# I2c.net
KiCad netlist of a schematic drawn in Altium Designer
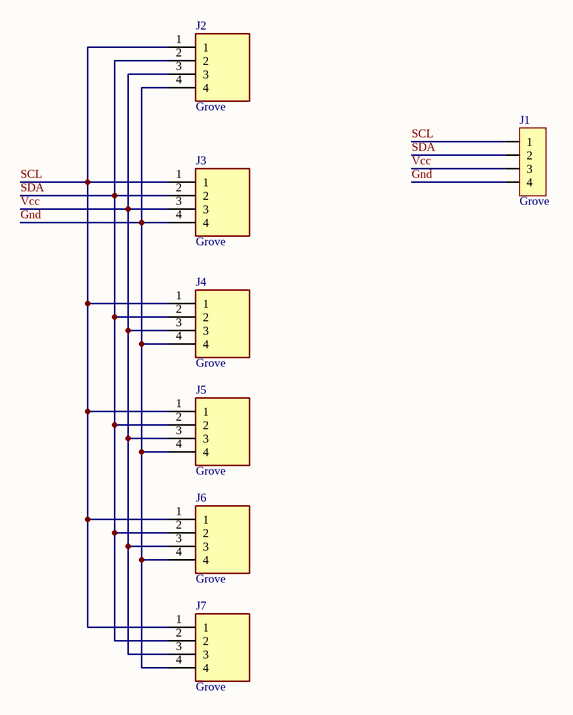
[diagram p0: I2c.SchDoc]

(export (version "E")
  (design (tool "Eeschema 10.0.6"))
  (components
    (comp (ref "J1")
      (value "Grove")
      (footprint "HDR/Header/4/2mm/BOX/SMD")
      (description "Header, 4-Pin")
      (libsource (lib "chipfc_altium_libs") (part "Header 4"))
    )
    (comp (ref "J2")
      (value "Grove")
      (footprint "SEEED_110990030")
      (description "GROVE 2MM 4PIN VERT CONN 10PCS")
      (fields (field (name "MP") "110990030") (field (name "MF") "Seeed Technology"))
      (libsource (lib "110990030") (part "110990030"))
    )
    (comp (ref "J3")
      (value "Grove")
      (footprint "SEEED_110990030")
      (description "GROVE 2MM 4PIN VERT CONN 10PCS")
      (fields (field (name "MP") "110990030") (field (name "MF") "Seeed Technology"))
      (libsource (lib "110990030") (part "110990030"))
    )
    (comp (ref "J4")
      (value "Grove")
      (footprint "SEEED_110990030")
      (description "GROVE 2MM 4PIN VERT CONN 10PCS")
      (fields (field (name "MP") "110990030") (field (name "MF") "Seeed Technology"))
      (libsource (lib "110990030") (part "110990030"))
    )
    (comp (ref "J5")
      (value "Grove")
      (footprint "SEEED_110990030")
      (description "GROVE 2MM 4PIN VERT CONN 10PCS")
      (fields (field (name "MP") "110990030") (field (name "MF") "Seeed Technology"))
      (libsource (lib "110990030") (part "110990030"))
    )
    (comp (ref "J6")
      (value "Grove")
      (footprint "SEEED_110990030")
      (description "GROVE 2MM 4PIN VERT CONN 10PCS")
      (fields (field (name "MP") "110990030") (field (name "MF") "Seeed Technology"))
      (libsource (lib "110990030") (part "110990030"))
    )
    (comp (ref "J7")
      (value "Grove")
      (footprint "SEEED_110990030")
      (description "GROVE 2MM 4PIN VERT CONN 10PCS")
      (fields (field (name "MP") "110990030") (field (name "MF") "Seeed Technology"))
      (libsource (lib "110990030") (part "110990030"))
    )
  )
  (nets
    (net (code "1") (name "/Gnd") (class "Default")
      (node (ref "J1") (pin "4") (pinfunction "4_4") (pintype "passive"))
      (node (ref "J2") (pin "4") (pinfunction "4_4") (pintype "passive"))
      (node (ref "J3") (pin "4") (pinfunction "4_4") (pintype "passive"))
      (node (ref "J4") (pin "4") (pinfunction "4_4") (pintype "passive"))
      (node (ref "J5") (pin "4") (pinfunction "4_4") (pintype "passive"))
      (node (ref "J6") (pin "4") (pinfunction "4_4") (pintype "passive"))
      (node (ref "J7") (pin "4") (pinfunction "4_4") (pintype "passive"))
    )
    (net (code "2") (name "/SCL") (class "Default")
      (node (ref "J1") (pin "1") (pinfunction "1_1") (pintype "passive"))
      (node (ref "J2") (pin "1") (pinfunction "1_1") (pintype "passive"))
      (node (ref "J3") (pin "1") (pinfunction "1_1") (pintype "passive"))
      (node (ref "J4") (pin "1") (pinfunction "1_1") (pintype "passive"))
      (node (ref "J5") (pin "1") (pinfunction "1_1") (pintype "passive"))
      (node (ref "J6") (pin "1") (pinfunction "1_1") (pintype "passive"))
      (node (ref "J7") (pin "1") (pinfunction "1_1") (pintype "passive"))
    )
    (net (code "3") (name "/SDA") (class "Default")
      (node (ref "J1") (pin "2") (pinfunction "2_2") (pintype "passive"))
      (node (ref "J2") (pin "2") (pinfunction "2_2") (pintype "passive"))
      (node (ref "J3") (pin "2") (pinfunction "2_2") (pintype "passive"))
      (node (ref "J4") (pin "2") (pinfunction "2_2") (pintype "passive"))
      (node (ref "J5") (pin "2") (pinfunction "2_2") (pintype "passive"))
      (node (ref "J6") (pin "2") (pinfunction "2_2") (pintype "passive"))
      (node (ref "J7") (pin "2") (pinfunction "2_2") (pintype "passive"))
    )
    (net (code "4") (name "/Vcc") (class "Default")
      (node (ref "J1") (pin "3") (pinfunction "3_3") (pintype "passive"))
      (node (ref "J2") (pin "3") (pinfunction "3_3") (pintype "passive"))
      (node (ref "J3") (pin "3") (pinfunction "3_3") (pintype "passive"))
      (node (ref "J4") (pin "3") (pinfunction "3_3") (pintype "passive"))
      (node (ref "J5") (pin "3") (pinfunction "3_3") (pintype "passive"))
      (node (ref "J6") (pin "3") (pinfunction "3_3") (pintype "passive"))
      (node (ref "J7") (pin "3") (pinfunction "3_3") (pintype "passive"))
    )
  )
)
